# LoRa_Test_Board_Sheet.net
KiCad netlist of a schematic drawn in Altium Designer
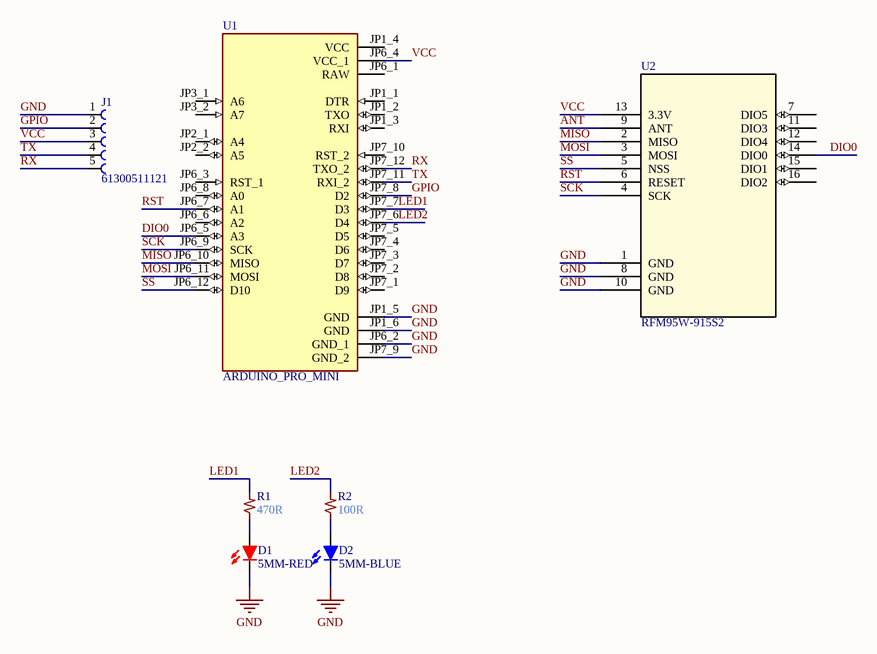
[diagram p0: LoRa_Test_Board_Sheet.SchDoc]

(export (version "E")
  (design (tool "Eeschema 10.0.6"))
  (components
    (comp (ref "D1")
      (value "5MM-RED")
      (footprint "LED5MM-RED")
      (description "LED RED 5MM")
      (libsource (lib "1_ozcan_Optoelectronics") (part "LED5MM-RED"))
    )
    (comp (ref "D2")
      (value "5MM-BLUE")
      (footprint "LED5MM-BLUE")
      (description "LED BLUE 5MM")
      (libsource (lib "1_ozcan_Optoelectronics") (part "LED5MM-BLUE"))
    )
    (comp (ref "J1")
      (value "61300511121")
      (footprint "61300511121")
      (description "Connector Header Through Hole 5 position 0.100 (2.54mm)")
      (fields (field (name "MF") "WÃ¼rth Elektronik"))
      (libsource (lib "5 Pin Header Male") (part "61300511121"))
    )
    (comp (ref "R1")
      (value "470R")
      (footprint "R0603")
      (description "RES SMD 470 OHM 1% 1/10W 0603")
      (fields (field (name "TOLERANCE") "1%"))
      (libsource (lib "1_ozcan_Resistors") (part "CRCW0603470RFKEA"))
    )
    (comp (ref "R2")
      (value "100R")
      (footprint "R0603")
      (description "RESISTOR, SURGE, 0603, 1%, 100R")
      (fields
        (field (name "MANUFACTURER") "Panasonic")
        (field (name "MANUFACTURER PART NUMBER") "ERJ-P03F1000V")
      )
      (libsource (lib "1_ozcan_Resistors") (part "ERJ-P03F1000V"))
    )
    (comp (ref "U1")
      (value "ARDUINO_PRO_MINI")
      (footprint "MODULE_ARDUINO_PRO_MINI")
      (fields (field (name "MP") "Arduino Pro Mini") (field (name "MF") "Arduino"))
      (libsource (lib "ARDUINO_PRO_MINI") (part "ARDUINO_PRO_MINI"))
    )
    (comp (ref "U2")
      (value "RFM95W-915S2")
      (footprint "IC16_RFM95W-915S2_RFS")
      (description "No Description Available")
      (fields (field (name "COPYRIGHT") "Copyright (C) 2023 Ultra Librarian. All rights reserved."))
      (libsource (lib "RFM95W-915S2") (part "RFM95W-915S2"))
    )
  )
  (nets
    (net (code "1") (name "/ANT") (class "Default")
      (node (ref "U2") (pin "9") (pinfunction "ANT_9") (pintype "passive"))
    )
    (net (code "2") (name "/DIO0") (class "Default")
      (node (ref "U1") (pin "JP6_5") (pinfunction "A3_JP6_5") (pintype "bidirectional"))
      (node (ref "U2") (pin "14") (pinfunction "DIO0_14") (pintype "bidirectional"))
    )
    (net (code "3") (name "/GPIO") (class "Default")
      (node (ref "J1") (pin "2") (pinfunction "2_2") (pintype "passive"))
      (node (ref "U1") (pin "JP7_8") (pinfunction "D2_JP7_8") (pintype "bidirectional"))
    )
    (net (code "4") (name "/LED1") (class "Default")
      (node (ref "R1") (pin "2") (pinfunction "2_2") (pintype "passive"))
      (node (ref "U1") (pin "JP7_7") (pinfunction "D3_JP7_7") (pintype "bidirectional"))
    )
    (net (code "5") (name "/LED2") (class "Default")
      (node (ref "R2") (pin "2") (pinfunction "2_2") (pintype "passive"))
      (node (ref "U1") (pin "JP7_6") (pinfunction "D4_JP7_6") (pintype "bidirectional"))
    )
    (net (code "6") (name "/MISO") (class "Default")
      (node (ref "U1") (pin "JP6_10") (pinfunction "MISO_JP6_10") (pintype "bidirectional"))
      (node (ref "U2") (pin "2") (pinfunction "MISO_2") (pintype "passive"))
    )
    (net (code "7") (name "/MOSI") (class "Default")
      (node (ref "U1") (pin "JP6_11") (pinfunction "MOSI_JP6_11") (pintype "bidirectional"))
      (node (ref "U2") (pin "3") (pinfunction "MOSI_3") (pintype "passive"))
    )
    (net (code "8") (name "/RST") (class "Default")
      (node (ref "U1") (pin "JP6_7") (pinfunction "A1_JP6_7") (pintype "bidirectional"))
      (node (ref "U2") (pin "6") (pinfunction "RESET_6") (pintype "passive"))
    )
    (net (code "9") (name "/RX") (class "Default")
      (node (ref "J1") (pin "5") (pinfunction "5_5") (pintype "passive"))
      (node (ref "U1") (pin "JP7_12") (pinfunction "TXO_2_JP7_12") (pintype "bidirectional"))
    )
    (net (code "10") (name "/SCK") (class "Default")
      (node (ref "U1") (pin "JP6_9") (pinfunction "SCK_JP6_9") (pintype "bidirectional"))
      (node (ref "U2") (pin "4") (pinfunction "SCK_4") (pintype "passive"))
    )
    (net (code "11") (name "/SS") (class "Default")
      (node (ref "U1") (pin "JP6_12") (pinfunction "D10_JP6_12") (pintype "bidirectional"))
      (node (ref "U2") (pin "5") (pinfunction "NSS_5") (pintype "passive"))
    )
    (net (code "12") (name "/TX") (class "Default")
      (node (ref "J1") (pin "4") (pinfunction "4_4") (pintype "passive"))
      (node (ref "U1") (pin "JP7_11") (pinfunction "RXI_2_JP7_11") (pintype "bidirectional"))
    )
    (net (code "13") (name "/VCC") (class "Default")
      (node (ref "J1") (pin "3") (pinfunction "3_3") (pintype "passive"))
      (node (ref "U1") (pin "JP6_4") (pinfunction "VCC_1_JP6_4") (pintype "power_in"))
      (node (ref "U2") (pin "13") (pinfunction "3.3V_13") (pintype "passive"))
    )
    (net (code "14") (name "GND") (class "Default")
      (node (ref "D1") (pin "C") (pinfunction "C_C") (pintype "passive"))
      (node (ref "D2") (pin "C") (pinfunction "C_C") (pintype "passive"))
      (node (ref "J1") (pin "1") (pinfunction "1_1") (pintype "passive"))
      (node (ref "U1") (pin "JP1_5") (pinfunction "GND_JP1_5") (pintype "power_in"))
      (node (ref "U1") (pin "JP1_6") (pinfunction "GND_JP1_6") (pintype "power_in"))
      (node (ref "U1") (pin "JP6_2") (pinfunction "GND_1_JP6_2") (pintype "power_in"))
      (node (ref "U1") (pin "JP7_9") (pinfunction "GND_2_JP7_9") (pintype "power_in"))
      (node (ref "U2") (pin "1") (pinfunction "GND_1") (pintype "passive"))
      (node (ref "U2") (pin "10") (pinfunction "GND_10") (pintype "passive"))
      (node (ref "U2") (pin "8") (pinfunction "GND_8") (pintype "passive"))
    )
    (net (code "15") (name "Net-(D1-PadA)") (class "Default")
      (node (ref "D1") (pin "A") (pinfunction "A_A") (pintype "passive"))
      (node (ref "R1") (pin "1") (pinfunction "1_1") (pintype "passive"))
    )
    (net (code "16") (name "Net-(D2-PadA)") (class "Default")
      (node (ref "D2") (pin "A") (pinfunction "A_A") (pintype "passive"))
      (node (ref "R2") (pin "1") (pinfunction "1_1") (pintype "passive"))
    )
    (net (code "17") (name "unconnected-(U1-A0-PadJP6_8)") (class "Default")
      (node (ref "U1") (pin "JP6_8") (pinfunction "A0_JP6_8") (pintype "bidirectional"))
    )
    (net (code "18") (name "unconnected-(U1-A2-PadJP6_6)") (class "Default")
      (node (ref "U1") (pin "JP6_6") (pinfunction "A2_JP6_6") (pintype "bidirectional"))
    )
    (net (code "19") (name "unconnected-(U1-A4-PadJP2_1)") (class "Default")
      (node (ref "U1") (pin "JP2_1") (pinfunction "A4_JP2_1") (pintype "bidirectional"))
    )
    (net (code "20") (name "unconnected-(U1-A5-PadJP2_2)") (class "Default")
      (node (ref "U1") (pin "JP2_2") (pinfunction "A5_JP2_2") (pintype "bidirectional"))
    )
    (net (code "21") (name "unconnected-(U1-A6-PadJP3_1)") (class "Default")
      (node (ref "U1") (pin "JP3_1") (pinfunction "A6_JP3_1") (pintype "input"))
    )
    (net (code "22") (name "unconnected-(U1-A7-PadJP3_2)") (class "Default")
      (node (ref "U1") (pin "JP3_2") (pinfunction "A7_JP3_2") (pintype "input"))
    )
    (net (code "23") (name "unconnected-(U1-D5-PadJP7_5)") (class "Default")
      (node (ref "U1") (pin "JP7_5") (pinfunction "D5_JP7_5") (pintype "bidirectional"))
    )
    (net (code "24") (name "unconnected-(U1-D6-PadJP7_4)") (class "Default")
      (node (ref "U1") (pin "JP7_4") (pinfunction "D6_JP7_4") (pintype "bidirectional"))
    )
    (net (code "25") (name "unconnected-(U1-D7-PadJP7_3)") (class "Default")
      (node (ref "U1") (pin "JP7_3") (pinfunction "D7_JP7_3") (pintype "bidirectional"))
    )
    (net (code "26") (name "unconnected-(U1-D8-PadJP7_2)") (class "Default")
      (node (ref "U1") (pin "JP7_2") (pinfunction "D8_JP7_2") (pintype "bidirectional"))
    )
    (net (code "27") (name "unconnected-(U1-D9-PadJP7_1)") (class "Default")
      (node (ref "U1") (pin "JP7_1") (pinfunction "D9_JP7_1") (pintype "bidirectional"))
    )
    (net (code "28") (name "unconnected-(U1-DTR-PadJP1_1)") (class "Default")
      (node (ref "U1") (pin "JP1_1") (pinfunction "DTR_JP1_1") (pintype "input"))
    )
    (net (code "29") (name "unconnected-(U1-RAW-PadJP6_1)") (class "Default")
      (node (ref "U1") (pin "JP6_1") (pinfunction "RAW_JP6_1") (pintype "power_in"))
    )
    (net (code "30") (name "unconnected-(U1-RST_1-PadJP6_3)") (class "Default")
      (node (ref "U1") (pin "JP6_3") (pinfunction "RST_1_JP6_3") (pintype "input"))
    )
    (net (code "31") (name "unconnected-(U1-RST_2-PadJP7_10)") (class "Default")
      (node (ref "U1") (pin "JP7_10") (pinfunction "RST_2_JP7_10") (pintype "input"))
    )
    (net (code "32") (name "unconnected-(U1-RXI-PadJP1_3)") (class "Default")
      (node (ref "U1") (pin "JP1_3") (pinfunction "RXI_JP1_3") (pintype "bidirectional"))
    )
    (net (code "33") (name "unconnected-(U1-TXO-PadJP1_2)") (class "Default")
      (node (ref "U1") (pin "JP1_2") (pinfunction "TXO_JP1_2") (pintype "bidirectional"))
    )
    (net (code "34") (name "unconnected-(U1-VCC-PadJP1_4)") (class "Default")
      (node (ref "U1") (pin "JP1_4") (pinfunction "VCC_JP1_4") (pintype "power_in"))
    )
    (net (code "35") (name "unconnected-(U2-DIO1-Pad15)") (class "Default")
      (node (ref "U2") (pin "15") (pinfunction "DIO1_15") (pintype "bidirectional"))
    )
    (net (code "36") (name "unconnected-(U2-DIO2-Pad16)") (class "Default")
      (node (ref "U2") (pin "16") (pinfunction "DIO2_16") (pintype "bidirectional"))
    )
    (net (code "37") (name "unconnected-(U2-DIO3-Pad11)") (class "Default")
      (node (ref "U2") (pin "11") (pinfunction "DIO3_11") (pintype "bidirectional"))
    )
    (net (code "38") (name "unconnected-(U2-DIO4-Pad12)") (class "Default")
      (node (ref "U2") (pin "12") (pinfunction "DIO4_12") (pintype "bidirectional"))
    )
    (net (code "39") (name "unconnected-(U2-DIO5-Pad7)") (class "Default")
      (node (ref "U2") (pin "7") (pinfunction "DIO5_7") (pintype "bidirectional"))
    )
  )
)
